# SY_HR08_MCU_SMT32_V1_1.net
KiCad netlist of a schematic drawn in Altium Designer
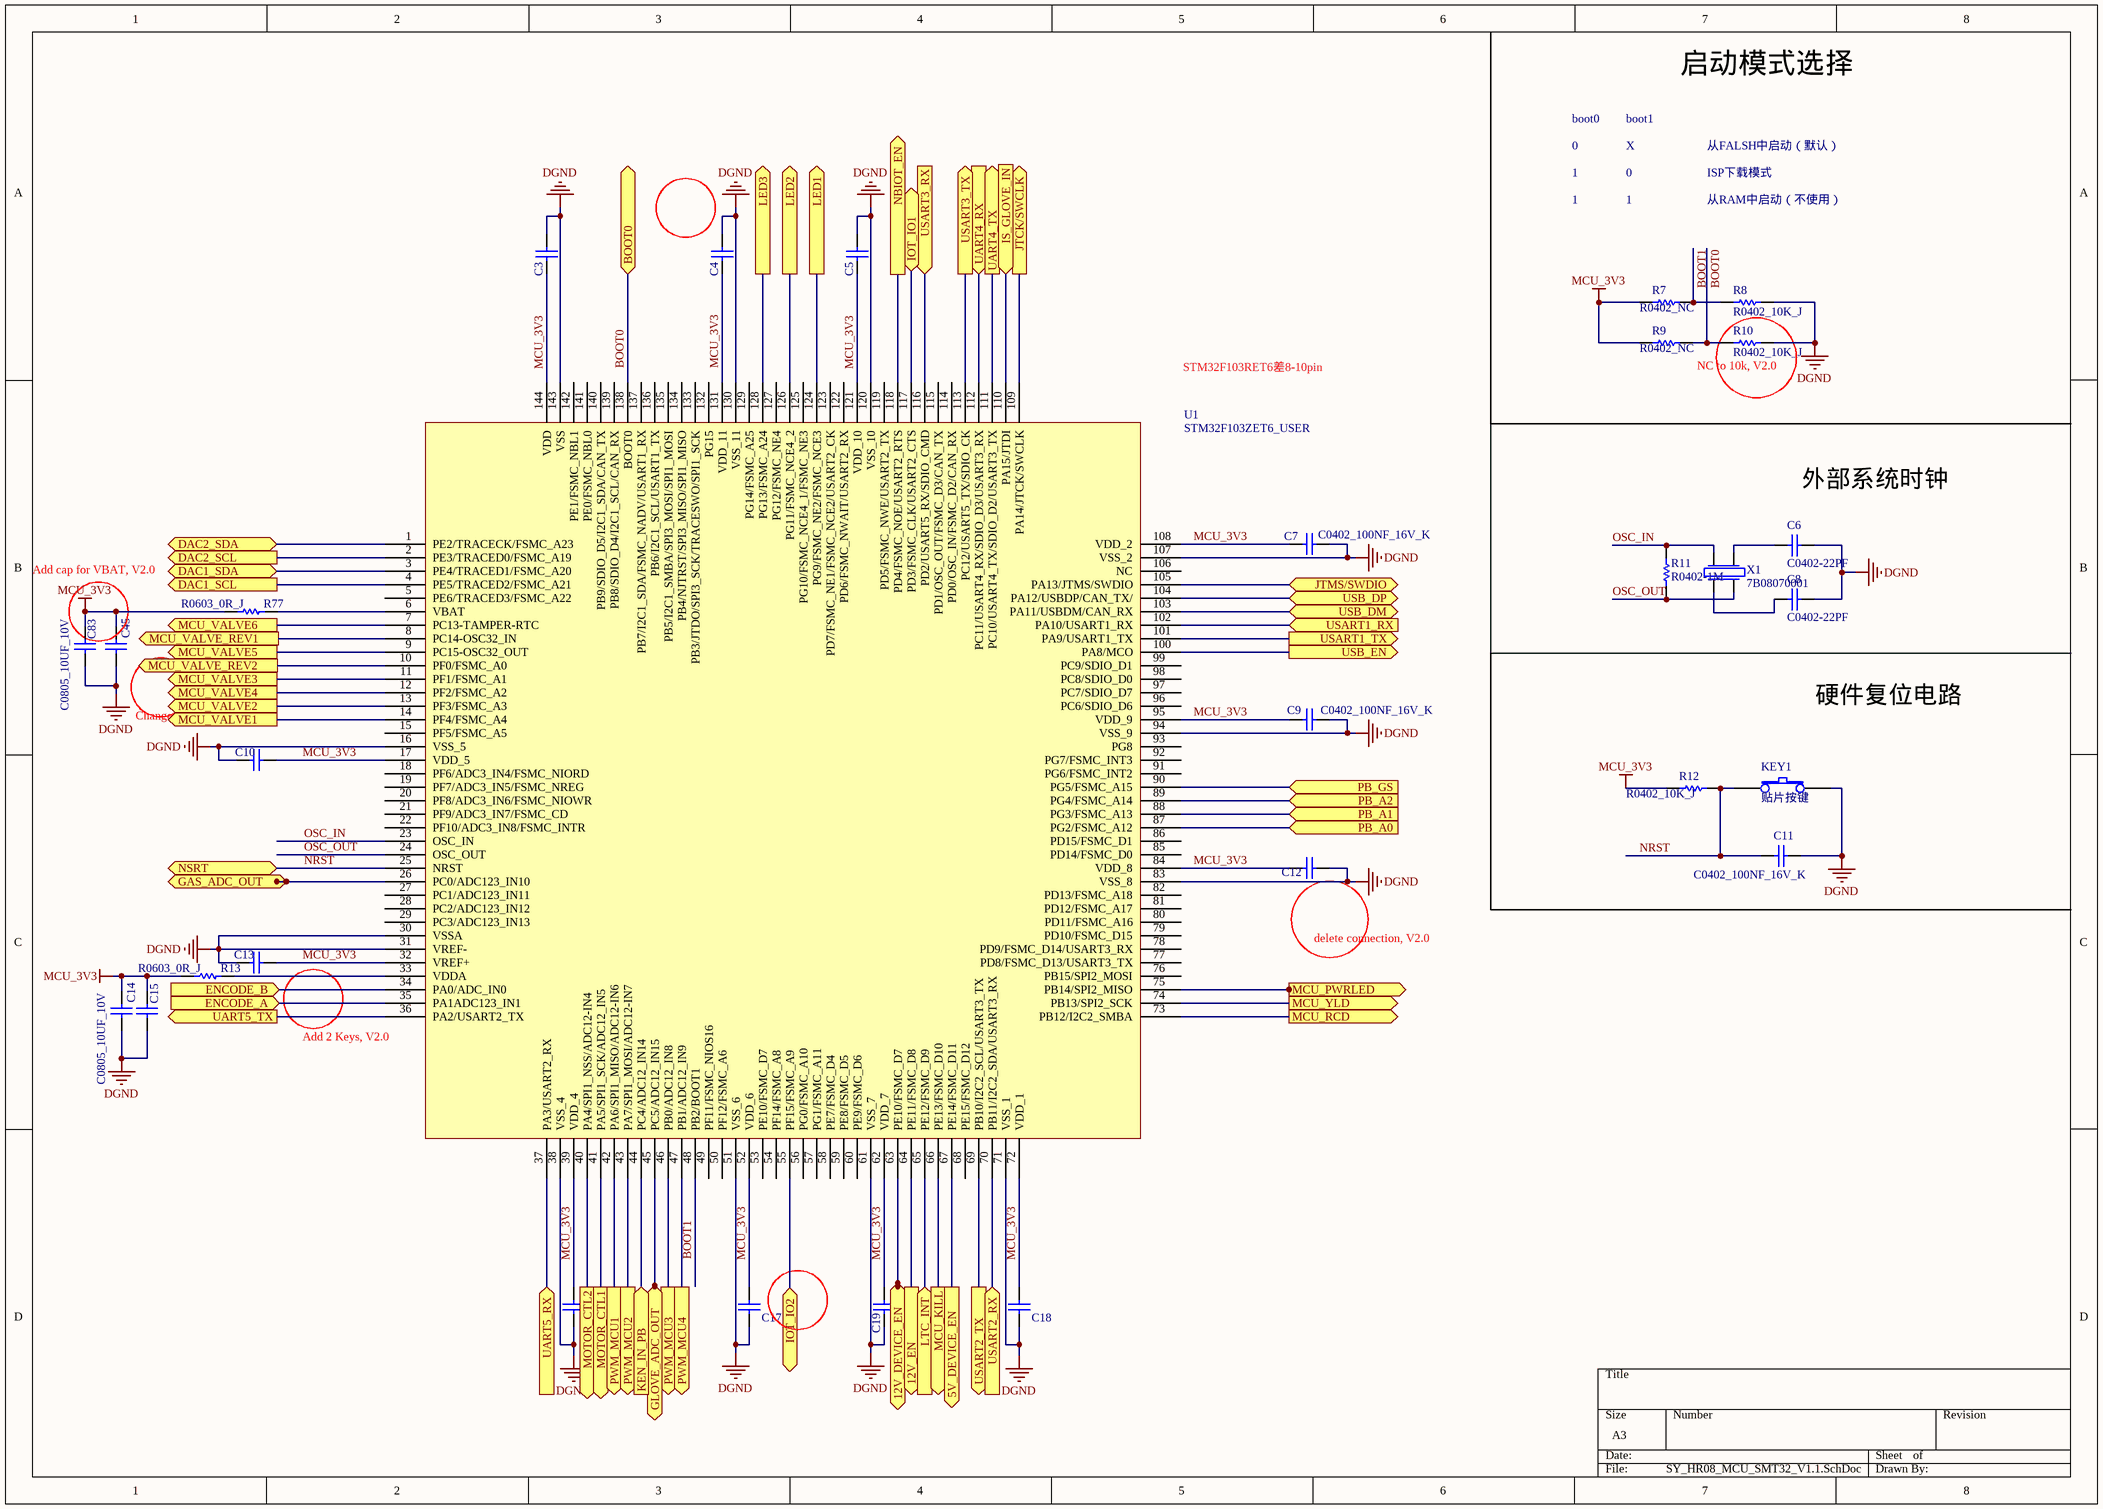
[diagram p0: SY_HR08_MCU_SMT32_V1.1.SchDoc]

(export (version "E")
  (design (tool "Eeschema 10.0.6"))
  (components
    (comp (ref "C3")
      (value "C0402_100NF_16V_K")
      (footprint "CAP0402_HQ")
      (description "电容_100nF_0402_X7R_16V_K")
      (libsource (lib "zhangky_sch") (part "C0402_100NF_16V_K"))
    )
    (comp (ref "C4")
      (value "C0402_100NF_16V_K")
      (footprint "CAP0402_HQ")
      (description "电容_100nF_0402_X7R_16V_K")
      (libsource (lib "zhangky_sch") (part "C0402_100NF_16V_K"))
    )
    (comp (ref "C5")
      (value "C0402_100NF_16V_K")
      (footprint "CAP0402_HQ")
      (description "电容_100nF_0402_X7R_16V_K")
      (libsource (lib "zhangky_sch") (part "C0402_100NF_16V_K"))
    )
    (comp (ref "C6")
      (value "C0402-22PF")
      (footprint "CAP0402_HQ")
      (description "电容_22pF_0402_C0G_50V_J")
      (libsource (lib "zhangky_sch") (part "C0402-22PF"))
    )
    (comp (ref "C7")
      (value "C0402_100NF_16V_K")
      (footprint "CAP0402_HQ")
      (description "电容_100nF_0402_X7R_16V_K")
      (libsource (lib "zhangky_sch") (part "C0402_100NF_16V_K"))
    )
    (comp (ref "C8")
      (value "C0402-22PF")
      (footprint "CAP0402_HQ")
      (description "电容_22pF_0402_C0G_50V_J")
      (libsource (lib "zhangky_sch") (part "C0402-22PF"))
    )
    (comp (ref "C9")
      (value "C0402_100NF_16V_K")
      (footprint "CAP0402_HQ")
      (description "电容_100nF_0402_X7R_16V_K")
      (libsource (lib "zhangky_sch") (part "C0402_100NF_16V_K"))
    )
    (comp (ref "C10")
      (value "C0402_100NF_16V_K")
      (footprint "CAP0402_HQ")
      (description "电容_100nF_0402_X7R_16V_K")
      (libsource (lib "zhangky_sch") (part "C0402_100NF_16V_K"))
    )
    (comp (ref "C11")
      (value "C0402_100NF_16V_K")
      (footprint "CAP0402_HQ")
      (description "电容_100nF_0402_X7R_16V_K")
      (libsource (lib "zhangky_sch") (part "C0402_100NF_16V_K"))
    )
    (comp (ref "C12")
      (value "C0402_100NF_16V_K")
      (footprint "CAP0402_HQ")
      (description "电容_100nF_0402_X7R_16V_K")
      (libsource (lib "zhangky_sch") (part "C0402_100NF_16V_K"))
    )
    (comp (ref "C13")
      (value "C0402_100NF_16V_K")
      (footprint "CAP0402_HQ")
      (description "电容_100nF_0402_X7R_16V_K")
      (libsource (lib "zhangky_sch") (part "C0402_100NF_16V_K"))
    )
    (comp (ref "C14")
      (value "C0805_10UF_10V")
      (footprint "CAP0805-B")
      (description "电容_10uF_0805_X5R_10V_K")
      (libsource (lib "zhangky_sch") (part "C0805_10UF_10V"))
    )
    (comp (ref "C15")
      (value "C0402_100NF_16V_K")
      (footprint "CAP0402_HQ")
      (description "电容_100nF_0402_X7R_16V_K")
      (libsource (lib "zhangky_sch") (part "C0402_100NF_16V_K"))
    )
    (comp (ref "C16")
      (value "C0402_100NF_16V_K")
      (footprint "CAP0402_HQ")
      (description "电容_100nF_0402_X7R_16V_K")
      (libsource (lib "zhangky_sch") (part "C0402_100NF_16V_K"))
    )
    (comp (ref "C17")
      (value "C0402_100NF_16V_K")
      (footprint "CAP0402_HQ")
      (description "电容_100nF_0402_X7R_16V_K")
      (libsource (lib "zhangky_sch") (part "C0402_100NF_16V_K"))
    )
    (comp (ref "C18")
      (value "C0402_100NF_16V_K")
      (footprint "CAP0402_HQ")
      (description "电容_100nF_0402_X7R_16V_K")
      (libsource (lib "zhangky_sch") (part "C0402_100NF_16V_K"))
    )
    (comp (ref "C19")
      (value "C0402_100NF_16V_K")
      (footprint "CAP0402_HQ")
      (description "电容_100nF_0402_X7R_16V_K")
      (libsource (lib "zhangky_sch") (part "C0402_100NF_16V_K"))
    )
    (comp (ref "C45")
      (value "C0805_10UF_10V")
      (footprint "CAP0805-B")
      (description "电容_10uF_0805_X5R_10V_K")
      (libsource (lib "zhangky_sch") (part "C0805_10UF_10V"))
    )
    (comp (ref "C83")
      (value "C0402_100NF_16V_K")
      (footprint "CAP0402_HQ")
      (description "电容_100nF_0402_X7R_16V_K")
      (libsource (lib "zhangky_sch") (part "C0402_100NF_16V_K"))
    )
    (comp (ref "KEY1")
      (value "贴片按键")
      (footprint "KEY_3x4x2")
      (description "KEY_3x4x2mm")
      (libsource (lib "zhangky_sch") (part "KEY_3x4x2"))
    )
    (comp (ref "R7")
      (value "R0402_NC")
      (footprint "RES0402_HQ_NC")
      (description "NC")
      (libsource (lib "zhangky_sch") (part "R0402_NC"))
    )
    (comp (ref "R8")
      (value "R0402_10K_J")
      (footprint "RES0402_HQ")
      (description "电阻10K(0402-0.0625W-J)")
      (libsource (lib "zhangky_sch") (part "R0402_10K_J"))
    )
    (comp (ref "R9")
      (value "R0402_NC")
      (footprint "RES0402_HQ_NC")
      (description "NC")
      (libsource (lib "zhangky_sch") (part "R0402_NC"))
    )
    (comp (ref "R10")
      (value "R0402_10K_J")
      (footprint "RES0402_HQ_NC")
      (description "NC")
      (libsource (lib "zhangky_sch") (part "R0402_NC"))
    )
    (comp (ref "R11")
      (value "R0402-1M")
      (footprint "RES0402_HQ")
      (description "电阻_1M(0402-0.0625W-J)")
      (libsource (lib "zhangky_sch") (part "R0402-1M"))
    )
    (comp (ref "R12")
      (value "R0402_10K_J")
      (footprint "RES0402_HQ")
      (description "电阻10K(0402-0.0625W-J)")
      (libsource (lib "zhangky_sch") (part "R0402_10K_J"))
    )
    (comp (ref "R13")
      (value "R0603_0R_J")
      (footprint "RES0603-A")
      (description "电阻0R(0603-0.1W-J)")
      (libsource (lib "zhangky_sch") (part "R0603_0R_J"))
    )
    (comp (ref "R77")
      (value "R0603_0R_J")
      (footprint "RES0603-A")
      (description "电阻0R(0603-0.1W-J)")
      (libsource (lib "zhangky_sch") (part "R0603_0R_J"))
    )
    (comp (ref "U1")
      (value "STM32F103ZET6_USER")
      (footprint "LQFP144_STM32F103")
      (libsource (lib "zhangky_sch") (part "STM32F103ZET6_USER"))
    )
    (comp (ref "X1")
      (value "7B08070001")
      (footprint "7B08070001")
      (description "TXC 5032 7B系列晶体")
      (fields (field (name "MANUFACTURER") "TXC"))
      (libsource (lib "zhangky_sch") (part "7B08070001"))
    )
  )
  (nets
    (net (code "1") (name "/5V_DEVICE_EN") (class "Default")
      (node (ref "U1") (pin "67") (pinfunction "PE14/FSMC_D11_67") (pintype "passive"))
    )
    (net (code "2") (name "/12V_DEVICE_EN") (class "Default")
      (node (ref "U1") (pin "63") (pinfunction "PE10/FSMC_D7_63") (pintype "passive"))
    )
    (net (code "3") (name "/12V_EN") (class "Default")
      (node (ref "U1") (pin "64") (pinfunction "PE11/FSMC_D8_64") (pintype "passive"))
    )
    (net (code "4") (name "/BOOT0") (class "Default")
      (node (ref "R10") (pin "1") (pinfunction "1_1") (pintype "passive"))
      (node (ref "R9") (pin "2") (pinfunction "2_2") (pintype "passive"))
      (node (ref "U1") (pin "138") (pinfunction "BOOT0_138") (pintype "passive"))
    )
    (net (code "5") (name "/BOOT1") (class "Default")
      (node (ref "R7") (pin "2") (pinfunction "2_2") (pintype "passive"))
      (node (ref "R8") (pin "1") (pinfunction "1_1") (pintype "passive"))
      (node (ref "U1") (pin "48") (pinfunction "PB2/BOOT1_48") (pintype "passive"))
    )
    (net (code "6") (name "/DAC1_SCL") (class "Default")
      (node (ref "U1") (pin "4") (pinfunction "PE5/TRACED2/FSMC_A21_4") (pintype "passive"))
    )
    (net (code "7") (name "/DAC1_SDA") (class "Default")
      (node (ref "U1") (pin "3") (pinfunction "PE4/TRACED1/FSMC_A20_3") (pintype "passive"))
    )
    (net (code "8") (name "/DAC2_SCL") (class "Default")
      (node (ref "U1") (pin "2") (pinfunction "PE3/TRACED0/FSMC_A19_2") (pintype "passive"))
    )
    (net (code "9") (name "/DAC2_SDA") (class "Default")
      (node (ref "U1") (pin "1") (pinfunction "PE2/TRACECK/FSMC_A23_1") (pintype "passive"))
    )
    (net (code "10") (name "/ENCODE_A") (class "Default")
      (node (ref "U1") (pin "35") (pinfunction "PA1ADC123_IN1_35") (pintype "passive"))
    )
    (net (code "11") (name "/ENCODE_B") (class "Default")
      (node (ref "U1") (pin "34") (pinfunction "PA0/ADC_IN0_34") (pintype "passive"))
    )
    (net (code "12") (name "/GAS_ADC_OUT") (class "Default")
      (node (ref "U1") (pin "26") (pinfunction "PC0/ADC123_IN10_26") (pintype "passive"))
    )
    (net (code "13") (name "/GLOVE_ADC_OUT") (class "Default")
      (node (ref "U1") (pin "45") (pinfunction "PC5/ADC12_IN15_45") (pintype "passive"))
    )
    (net (code "14") (name "/IOT_IO1") (class "Default")
      (node (ref "U1") (pin "117") (pinfunction "PD3/FSMC_CLK/USART2_CTS_117") (pintype "passive"))
    )
    (net (code "15") (name "/IOT_IO2") (class "Default")
      (node (ref "U1") (pin "55") (pinfunction "PF15/FSMC_A9_55") (pintype "passive"))
    )
    (net (code "16") (name "/IS_GLOVE_IN") (class "Default")
      (node (ref "U1") (pin "110") (pinfunction "PA15/JTDI_110") (pintype "passive"))
    )
    (net (code "17") (name "/JTCK{slash}SWCLK") (class "Default")
      (node (ref "U1") (pin "109") (pinfunction "PA14/JTCK/SWCLK_109") (pintype "passive"))
    )
    (net (code "18") (name "/JTMS{slash}SWDIO") (class "Default")
      (node (ref "U1") (pin "105") (pinfunction "PA13/JTMS/SWDIO_105") (pintype "passive"))
    )
    (net (code "19") (name "/KEN_IN_PB") (class "Default")
      (node (ref "U1") (pin "44") (pinfunction "PC4/ADC12_IN14_44") (pintype "passive"))
    )
    (net (code "20") (name "/LED1") (class "Default")
      (node (ref "U1") (pin "124") (pinfunction "PG9/FSMC_NE2/FSMC_NCE3_124") (pintype "passive"))
    )
    (net (code "21") (name "/LED2") (class "Default")
      (node (ref "U1") (pin "126") (pinfunction "PG11/FSMC_NCE4_2_126") (pintype "passive"))
    )
    (net (code "22") (name "/LED3") (class "Default")
      (node (ref "U1") (pin "128") (pinfunction "PG13/FSMC_A24_128") (pintype "passive"))
    )
    (net (code "23") (name "/LTC_INT") (class "Default")
      (node (ref "U1") (pin "65") (pinfunction "PE12/FSMC_D9_65") (pintype "passive"))
    )
    (net (code "24") (name "/MCU_KILL") (class "Default")
      (node (ref "U1") (pin "66") (pinfunction "PE13/FSMC_D10_66") (pintype "passive"))
    )
    (net (code "25") (name "/MCU_PWRLED") (class "Default")
      (node (ref "U1") (pin "75") (pinfunction "PB14/SPI2_MISO_75") (pintype "passive"))
    )
    (net (code "26") (name "/MCU_RCD") (class "Default")
      (node (ref "U1") (pin "73") (pinfunction "PB12/I2C2_SMBA_73") (pintype "passive"))
    )
    (net (code "27") (name "/MCU_VALVE1") (class "Default")
      (node (ref "U1") (pin "14") (pinfunction "PF4/FSMC_A4_14") (pintype "passive"))
    )
    (net (code "28") (name "/MCU_VALVE2") (class "Default")
      (node (ref "U1") (pin "13") (pinfunction "PF3/FSMC_A3_13") (pintype "passive"))
    )
    (net (code "29") (name "/MCU_VALVE3") (class "Default")
      (node (ref "U1") (pin "11") (pinfunction "PF1/FSMC_A1_11") (pintype "passive"))
    )
    (net (code "30") (name "/MCU_VALVE4") (class "Default")
      (node (ref "U1") (pin "12") (pinfunction "PF2/FSMC_A2_12") (pintype "passive"))
    )
    (net (code "31") (name "/MCU_VALVE5") (class "Default")
      (node (ref "U1") (pin "9") (pinfunction "PC15-OSC32_OUT_9") (pintype "passive"))
    )
    (net (code "32") (name "/MCU_VALVE6") (class "Default")
      (node (ref "U1") (pin "7") (pinfunction "PC13-TAMPER-RTC_7") (pintype "passive"))
    )
    (net (code "33") (name "/MCU_VALVE_REV1") (class "Default")
      (node (ref "U1") (pin "8") (pinfunction "PC14-OSC32_IN_8") (pintype "passive"))
    )
    (net (code "34") (name "/MCU_VALVE_REV2") (class "Default")
      (node (ref "U1") (pin "10") (pinfunction "PF0/FSMC_A0_10") (pintype "passive"))
    )
    (net (code "35") (name "/MCU_YLD") (class "Default")
      (node (ref "U1") (pin "74") (pinfunction "PB13/SPI2_SCK_74") (pintype "passive"))
    )
    (net (code "36") (name "/MOTOR_CTL1") (class "Default")
      (node (ref "U1") (pin "41") (pinfunction "PA5/SPI1_SCK/ADC12_IN5_41") (pintype "passive"))
    )
    (net (code "37") (name "/MOTOR_CTL2") (class "Default")
      (node (ref "U1") (pin "40") (pinfunction "PA4/SPI1_NSS/ADC12-IN4_40") (pintype "passive"))
    )
    (net (code "38") (name "/NBIOT_EN") (class "Default")
      (node (ref "U1") (pin "118") (pinfunction "PD4/FSMC_NOE/USART2_RTS_118") (pintype "passive"))
    )
    (net (code "39") (name "/NRST") (class "Default")
      (node (ref "C11") (pin "1") (pinfunction "1_1") (pintype "passive"))
      (node (ref "KEY1") (pin "1") (pinfunction "1_1") (pintype "passive"))
      (node (ref "R12") (pin "2") (pinfunction "2_2") (pintype "passive"))
      (node (ref "U1") (pin "25") (pinfunction "NRST_25") (pintype "passive"))
    )
    (net (code "40") (name "/OSC_IN") (class "Default")
      (node (ref "R11") (pin "2") (pinfunction "2_2") (pintype "passive"))
      (node (ref "U1") (pin "23") (pinfunction "OSC_IN_23") (pintype "passive"))
      (node (ref "X1") (pin "3") (pinfunction "3_3") (pintype "passive"))
    )
    (net (code "41") (name "/OSC_OUT") (class "Default")
      (node (ref "R11") (pin "1") (pinfunction "1_1") (pintype "passive"))
      (node (ref "U1") (pin "24") (pinfunction "OSC_OUT_24") (pintype "passive"))
      (node (ref "X1") (pin "1") (pinfunction "1_1") (pintype "passive"))
    )
    (net (code "42") (name "/PB_A0") (class "Default")
      (node (ref "U1") (pin "87") (pinfunction "PG2/FSMC_A12_87") (pintype "passive"))
    )
    (net (code "43") (name "/PB_A1") (class "Default")
      (node (ref "U1") (pin "88") (pinfunction "PG3/FSMC_A13_88") (pintype "passive"))
    )
    (net (code "44") (name "/PB_A2") (class "Default")
      (node (ref "U1") (pin "89") (pinfunction "PG4/FSMC_A14_89") (pintype "passive"))
    )
    (net (code "45") (name "/PB_GS") (class "Default")
      (node (ref "U1") (pin "90") (pinfunction "PG5/FSMC_A15_90") (pintype "passive"))
    )
    (net (code "46") (name "/PWM_MCU1") (class "Default")
      (node (ref "U1") (pin "42") (pinfunction "PA6/SPI1_MISO/ADC12-IN6_42") (pintype "passive"))
    )
    (net (code "47") (name "/PWM_MCU2") (class "Default")
      (node (ref "U1") (pin "43") (pinfunction "PA7/SPI1_MOSI/ADC12-IN7_43") (pintype "passive"))
    )
    (net (code "48") (name "/PWM_MCU3") (class "Default")
      (node (ref "U1") (pin "46") (pinfunction "PB0/ADC12_IN8_46") (pintype "passive"))
    )
    (net (code "49") (name "/PWM_MCU4") (class "Default")
      (node (ref "U1") (pin "47") (pinfunction "PB1/ADC12_IN9_47") (pintype "passive"))
    )
    (net (code "50") (name "/UART4_RX") (class "Default")
      (node (ref "U1") (pin "112") (pinfunction "PC11/USART4_RX/SDIO_D3/USART3_RX_112") (pintype "passive"))
    )
    (net (code "51") (name "/UART4_TX") (class "Default")
      (node (ref "U1") (pin "111") (pinfunction "PC10/USART4_TX/SDIO_D2/USART3_TX_111") (pintype "passive"))
    )
    (net (code "52") (name "/UART5_RX") (class "Default")
      (node (ref "U1") (pin "37") (pinfunction "PA3/USART2_RX_37") (pintype "passive"))
    )
    (net (code "53") (name "/UART5_TX") (class "Default")
      (node (ref "U1") (pin "36") (pinfunction "PA2/USART2_TX_36") (pintype "passive"))
    )
    (net (code "54") (name "/USART1_RX") (class "Default")
      (node (ref "U1") (pin "102") (pinfunction "PA10/USART1_RX_102") (pintype "passive"))
    )
    (net (code "55") (name "/USART1_TX") (class "Default")
      (node (ref "U1") (pin "101") (pinfunction "PA9/USART1_TX_101") (pintype "passive"))
    )
    (net (code "56") (name "/USART2_RX") (class "Default")
      (node (ref "U1") (pin "70") (pinfunction "PB11/I2C2_SDA/USART3_RX_70") (pintype "passive"))
    )
    (net (code "57") (name "/USART2_TX") (class "Default")
      (node (ref "U1") (pin "69") (pinfunction "PB10/I2C2_SCL/USART3_TX_69") (pintype "passive"))
    )
    (net (code "58") (name "/USART3_RX") (class "Default")
      (node (ref "U1") (pin "116") (pinfunction "PD2/USART5_RX/SDIO_CMD_116") (pintype "passive"))
    )
    (net (code "59") (name "/USART3_TX") (class "Default")
      (node (ref "U1") (pin "113") (pinfunction "PC12/USART5_TX/SDIO_CK_113") (pintype "passive"))
    )
    (net (code "60") (name "/USB_DM") (class "Default")
      (node (ref "U1") (pin "103") (pinfunction "PA11/USBDM/CAN_RX_103") (pintype "passive"))
    )
    (net (code "61") (name "/USB_DP") (class "Default")
      (node (ref "U1") (pin "104") (pinfunction "PA12/USBDP/CAN_TX/_104") (pintype "passive"))
    )
    (net (code "62") (name "/USB_EN") (class "Default")
      (node (ref "U1") (pin "100") (pinfunction "PA8/MCO_100") (pintype "passive"))
    )
    (net (code "63") (name "DGND") (class "Default")
      (node (ref "C10") (pin "2") (pinfunction "2_2") (pintype "passive"))
      (node (ref "C11") (pin "2") (pinfunction "2_2") (pintype "passive"))
      (node (ref "C12") (pin "2") (pinfunction "2_2") (pintype "passive"))
      (node (ref "C13") (pin "2") (pinfunction "2_2") (pintype "passive"))
      (node (ref "C14") (pin "1") (pinfunction "1_1") (pintype "passive"))
      (node (ref "C15") (pin "2") (pinfunction "2_2") (pintype "passive"))
      (node (ref "C16") (pin "2") (pinfunction "2_2") (pintype "passive"))
      (node (ref "C17") (pin "2") (pinfunction "2_2") (pintype "passive"))
      (node (ref "C18") (pin "2") (pinfunction "2_2") (pintype "passive"))
      (node (ref "C19") (pin "2") (pinfunction "2_2") (pintype "passive"))
      (node (ref "C3") (pin "2") (pinfunction "2_2") (pintype "passive"))
      (node (ref "C4") (pin "2") (pinfunction "2_2") (pintype "passive"))
      (node (ref "C45") (pin "1") (pinfunction "1_1") (pintype "passive"))
      (node (ref "C5") (pin "2") (pinfunction "2_2") (pintype "passive"))
      (node (ref "C6") (pin "2") (pinfunction "2_2") (pintype "passive"))
      (node (ref "C7") (pin "2") (pinfunction "2_2") (pintype "passive"))
      (node (ref "C8") (pin "2") (pinfunction "2_2") (pintype "passive"))
      (node (ref "C83") (pin "2") (pinfunction "2_2") (pintype "passive"))
      (node (ref "C9") (pin "2") (pinfunction "2_2") (pintype "passive"))
      (node (ref "KEY1") (pin "2") (pinfunction "2_2") (pintype "passive"))
      (node (ref "R10") (pin "2") (pinfunction "2_2") (pintype "passive"))
      (node (ref "R8") (pin "2") (pinfunction "2_2") (pintype "passive"))
      (node (ref "U1") (pin "107") (pinfunction "VSS_2_107") (pintype "passive"))
      (node (ref "U1") (pin "120") (pinfunction "VSS_10_120") (pintype "passive"))
      (node (ref "U1") (pin "130") (pinfunction "VSS_11_130") (pintype "passive"))
      (node (ref "U1") (pin "143") (pinfunction "VSS_143") (pintype "passive"))
      (node (ref "U1") (pin "16") (pinfunction "VSS_5_16") (pintype "passive"))
      (node (ref "U1") (pin "30") (pinfunction "VSSA_30") (pintype "passive"))
      (node (ref "U1") (pin "31") (pinfunction "VREF-_31") (pintype "passive"))
      (node (ref "U1") (pin "38") (pinfunction "VSS_4_38") (pintype "passive"))
      (node (ref "U1") (pin "51") (pinfunction "VSS_6_51") (pintype "passive"))
      (node (ref "U1") (pin "61") (pinfunction "VSS_7_61") (pintype "passive"))
      (node (ref "U1") (pin "71") (pinfunction "VSS_1_71") (pintype "passive"))
      (node (ref "U1") (pin "83") (pinfunction "VSS_8_83") (pintype "passive"))
      (node (ref "U1") (pin "94") (pinfunction "VSS_9_94") (pintype "passive"))
    )
    (net (code "64") (name "MCU_3V3") (class "Default")
      (node (ref "C10") (pin "1") (pinfunction "1_1") (pintype "passive"))
      (node (ref "C12") (pin "1") (pinfunction "1_1") (pintype "passive"))
      (node (ref "C13") (pin "1") (pinfunction "1_1") (pintype "passive"))
      (node (ref "C14") (pin "2") (pinfunction "2_2") (pintype "passive"))
      (node (ref "C15") (pin "1") (pinfunction "1_1") (pintype "passive"))
      (node (ref "C16") (pin "1") (pinfunction "1_1") (pintype "passive"))
      (node (ref "C17") (pin "1") (pinfunction "1_1") (pintype "passive"))
      (node (ref "C18") (pin "1") (pinfunction "1_1") (pintype "passive"))
      (node (ref "C19") (pin "1") (pinfunction "1_1") (pintype "passive"))
      (node (ref "C3") (pin "1") (pinfunction "1_1") (pintype "passive"))
      (node (ref "C4") (pin "1") (pinfunction "1_1") (pintype "passive"))
      (node (ref "C45") (pin "2") (pinfunction "2_2") (pintype "passive"))
      (node (ref "C5") (pin "1") (pinfunction "1_1") (pintype "passive"))
      (node (ref "C7") (pin "1") (pinfunction "1_1") (pintype "passive"))
      (node (ref "C83") (pin "1") (pinfunction "1_1") (pintype "passive"))
      (node (ref "C9") (pin "1") (pinfunction "1_1") (pintype "passive"))
      (node (ref "R12") (pin "1") (pinfunction "1_1") (pintype "passive"))
      (node (ref "R13") (pin "1") (pinfunction "1_1") (pintype "passive"))
      (node (ref "R7") (pin "1") (pinfunction "1_1") (pintype "passive"))
      (node (ref "R77") (pin "1") (pinfunction "1_1") (pintype "passive"))
      (node (ref "R9") (pin "1") (pinfunction "1_1") (pintype "passive"))
      (node (ref "U1") (pin "108") (pinfunction "VDD_2_108") (pintype "passive"))
      (node (ref "U1") (pin "121") (pinfunction "VDD_10_121") (pintype "passive"))
      (node (ref "U1") (pin "131") (pinfunction "VDD_11_131") (pintype "passive"))
      (node (ref "U1") (pin "144") (pinfunction "VDD_144") (pintype "passive"))
      (node (ref "U1") (pin "17") (pinfunction "VDD_5_17") (pintype "passive"))
      (node (ref "U1") (pin "32") (pinfunction "VREF+_32") (pintype "passive"))
      (node (ref "U1") (pin "39") (pinfunction "VDD_4_39") (pintype "passive"))
      (node (ref "U1") (pin "52") (pinfunction "VDD_6_52") (pintype "passive"))
      (node (ref "U1") (pin "62") (pinfunction "VDD_7_62") (pintype "passive"))
      (node (ref "U1") (pin "72") (pinfunction "VDD_1_72") (pintype "passive"))
      (node (ref "U1") (pin "84") (pinfunction "VDD_8_84") (pintype "passive"))
      (node (ref "U1") (pin "95") (pinfunction "VDD_9_95") (pintype "passive"))
    )
    (net (code "65") (name "Net-(C6-Pad1)") (class "Default")
      (node (ref "C6") (pin "1") (pinfunction "1_1") (pintype "passive"))
      (node (ref "X1") (pin "2") (pinfunction "2_2") (pintype "passive"))
    )
    (net (code "66") (name "Net-(C8-Pad1)") (class "Default")
      (node (ref "C8") (pin "1") (pinfunction "1_1") (pintype "passive"))
      (node (ref "X1") (pin "4") (pinfunction "4_4") (pintype "passive"))
    )
    (net (code "67") (name "Net-(U1-VBAT)") (class "Default")
      (node (ref "R77") (pin "2") (pinfunction "2_2") (pintype "passive"))
      (node (ref "U1") (pin "6") (pinfunction "VBAT_6") (pintype "passive"))
    )
    (net (code "68") (name "Net-(U1-VDDA)") (class "Default")
      (node (ref "R13") (pin "2") (pinfunction "2_2") (pintype "passive"))
      (node (ref "U1") (pin "33") (pinfunction "VDDA_33") (pintype "passive"))
    )
    (net (code "69") (name "unconnected-(U1-NC-Pad106)") (class "Default")
      (node (ref "U1") (pin "106") (pinfunction "NC_106") (pintype "passive"))
    )
    (net (code "70") (name "unconnected-(U1-PB3{slash}JTDO{slash}SPI3_SCK{slash}TRACESWO{slash}SPI1_SCK-Pad133)") (class "Default")
      (node (ref "U1") (pin "133") (pinfunction "PB3/JTDO/SPI3_SCK/TRACESWO/SPI1_SCK_133") (pintype "passive"))
    )
    (net (code "71") (name "unconnected-(U1-PB4{slash}NJTRST{slash}SPI3_MISO{slash}SPI1_MISO-Pad134)") (class "Default")
      (node (ref "U1") (pin "134") (pinfunction "PB4/NJTRST/SPI3_MISO/SPI1_MISO_134") (pintype "passive"))
    )
    (net (code "72") (name "unconnected-(U1-PB5{slash}I2C1_SMBA{slash}SPI3_MOSI{slash}SPI1_MOSI-Pad135)") (class "Default")
      (node (ref "U1") (pin "135") (pinfunction "PB5/I2C1_SMBA/SPI3_MOSI/SPI1_MOSI_135") (pintype "passive"))
    )
    (net (code "73") (name "unconnected-(U1-PB6{slash}I2C1_SCL{slash}USART1_TX-Pad136)") (class "Default")
      (node (ref "U1") (pin "136") (pinfunction "PB6/I2C1_SCL/USART1_TX_136") (pintype "passive"))
    )
    (net (code "74") (name "unconnected-(U1-PB7{slash}I2C1_SDA{slash}FSMC_NADV{slash}USART1_RX-Pad137)") (class "Default")
      (node (ref "U1") (pin "137") (pinfunction "PB7/I2C1_SDA/FSMC_NADV/USART1_RX_137") (pintype "passive"))
    )
    (net (code "75") (name "unconnected-(U1-PB8{slash}SDIO_D4{slash}I2C1_SCL{slash}CAN_RX-Pad139)") (class "Default")
      (node (ref "U1") (pin "139") (pinfunction "PB8/SDIO_D4/I2C1_SCL/CAN_RX_139") (pintype "passive"))
    )
    (net (code "76") (name "unconnected-(U1-PB9{slash}SDIO_D5{slash}I2C1_SDA{slash}CAN_TX-Pad140)") (class "Default")
      (node (ref "U1") (pin "140") (pinfunction "PB9/SDIO_D5/I2C1_SDA/CAN_TX_140") (pintype "passive"))
    )
    (net (code "77") (name "unconnected-(U1-PB15{slash}SPI2_MOSI-Pad76)") (class "Default")
      (node (ref "U1") (pin "76") (pinfunction "PB15/SPI2_MOSI_76") (pintype "passive"))
    )
    (net (code "78") (name "unconnected-(U1-PC1{slash}ADC123_IN11-Pad27)") (class "Default")
      (node (ref "U1") (pin "27") (pinfunction "PC1/ADC123_IN11_27") (pintype "passive"))
    )
    (net (code "79") (name "unconnected-(U1-PC2{slash}ADC123_IN12-Pad28)") (class "Default")
      (node (ref "U1") (pin "28") (pinfunction "PC2/ADC123_IN12_28") (pintype "passive"))
    )
    (net (code "80") (name "unconnected-(U1-PC3{slash}ADC123_IN13-Pad29)") (class "Default")
      (node (ref "U1") (pin "29") (pinfunction "PC3/ADC123_IN13_29") (pintype "passive"))
    )
    (net (code "81") (name "unconnected-(U1-PC6{slash}SDIO_D6-Pad96)") (class "Default")
      (node (ref "U1") (pin "96") (pinfunction "PC6/SDIO_D6_96") (pintype "passive"))
    )
    (net (code "82") (name "unconnected-(U1-PC7{slash}SDIO_D7-Pad97)") (class "Default")
      (node (ref "U1") (pin "97") (pinfunction "PC7/SDIO_D7_97") (pintype "passive"))
    )
    (net (code "83") (name "unconnected-(U1-PC8{slash}SDIO_D0-Pad98)") (class "Default")
      (node (ref "U1") (pin "98") (pinfunction "PC8/SDIO_D0_98") (pintype "passive"))
    )
    (net (code "84") (name "unconnected-(U1-PC9{slash}SDIO_D1-Pad99)") (class "Default")
      (node (ref "U1") (pin "99") (pinfunction "PC9/SDIO_D1_99") (pintype "passive"))
    )
    (net (code "85") (name "unconnected-(U1-PD0{slash}OSC_IN{slash}FSMC_D2{slash}CAN_RX-Pad114)") (class "Default")
      (node (ref "U1") (pin "114") (pinfunction "PD0/OSC_IN/FSMC_D2/CAN_RX_114") (pintype "passive"))
    )
    (net (code "86") (name "unconnected-(U1-PD1{slash}OSC_OUT{slash}FSMC_D3{slash}CAN_TX-Pad115)") (class "Default")
      (node (ref "U1") (pin "115") (pinfunction "PD1/OSC_OUT/FSMC_D3/CAN_TX_115") (pintype "passive"))
    )
    (net (code "87") (name "unconnected-(U1-PD5{slash}FSMC_NWE{slash}USART2_TX-Pad119)") (class "Default")
      (node (ref "U1") (pin "119") (pinfunction "PD5/FSMC_NWE/USART2_TX_119") (pintype "passive"))
    )
    (net (code "88") (name "unconnected-(U1-PD6{slash}FSMC_NWAIT{slash}USART2_RX-Pad122)") (class "Default")
      (node (ref "U1") (pin "122") (pinfunction "PD6/FSMC_NWAIT/USART2_RX_122") (pintype "passive"))
    )
    (net (code "89") (name "unconnected-(U1-PD7{slash}FSMC_NE1{slash}FSMC_NCE2{slash}USART2_CK-Pad123)") (class "Default")
      (node (ref "U1") (pin "123") (pinfunction "PD7/FSMC_NE1/FSMC_NCE2/USART2_CK_123") (pintype "passive"))
    )
    (net (code "90") (name "unconnected-(U1-PD8{slash}FSMC_D13{slash}USART3_TX-Pad77)") (class "Default")
      (node (ref "U1") (pin "77") (pinfunction "PD8/FSMC_D13/USART3_TX_77") (pintype "passive"))
    )
    (net (code "91") (name "unconnected-(U1-PD9{slash}FSMC_D14{slash}USART3_RX-Pad78)") (class "Default")
      (node (ref "U1") (pin "78") (pinfunction "PD9/FSMC_D14/USART3_RX_78") (pintype "passive"))
    )
    (net (code "92") (name "unconnected-(U1-PD10{slash}FSMC_D15-Pad79)") (class "Default")
      (node (ref "U1") (pin "79") (pinfunction "PD10/FSMC_D15_79") (pintype "passive"))
    )
    (net (code "93") (name "unconnected-(U1-PD11{slash}FSMC_A16-Pad80)") (class "Default")
      (node (ref "U1") (pin "80") (pinfunction "PD11/FSMC_A16_80") (pintype "passive"))
    )
    (net (code "94") (name "unconnected-(U1-PD12{slash}FSMC_A17-Pad81)") (class "Default")
      (node (ref "U1") (pin "81") (pinfunction "PD12/FSMC_A17_81") (pintype "passive"))
    )
    (net (code "95") (name "unconnected-(U1-PD13{slash}FSMC_A18-Pad82)") (class "Default")
      (node (ref "U1") (pin "82") (pinfunction "PD13/FSMC_A18_82") (pintype "passive"))
    )
    (net (code "96") (name "unconnected-(U1-PD14{slash}FSMC_D0-Pad85)") (class "Default")
      (node (ref "U1") (pin "85") (pinfunction "PD14/FSMC_D0_85") (pintype "passive"))
    )
    (net (code "97") (name "unconnected-(U1-PD15{slash}FSMC_D1-Pad86)") (class "Default")
      (node (ref "U1") (pin "86") (pinfunction "PD15/FSMC_D1_86") (pintype "passive"))
    )
    (net (code "98") (name "unconnected-(U1-PE0{slash}FSMC_NBL0-Pad141)") (class "Default")
      (node (ref "U1") (pin "141") (pinfunction "PE0/FSMC_NBL0_141") (pintype "passive"))
    )
    (net (code "99") (name "unconnected-(U1-PE1{slash}FSMC_NBL1-Pad142)") (class "Default")
      (node (ref "U1") (pin "142") (pinfunction "PE1/FSMC_NBL1_142") (pintype "passive"))
    )
    (net (code "100") (name "unconnected-(U1-PE6{slash}TRACED3{slash}FSMC_A22-Pad5)") (class "Default")
      (node (ref "U1") (pin "5") (pinfunction "PE6/TRACED3/FSMC_A22_5") (pintype "passive"))
    )
    (net (code "101") (name "unconnected-(U1-PE7{slash}FSMC_D4-Pad58)") (class "Default")
      (node (ref "U1") (pin "58") (pinfunction "PE7/FSMC_D4_58") (pintype "passive"))
    )
    (net (code "102") (name "unconnected-(U1-PE8{slash}FSMC_D5-Pad59)") (class "Default")
      (node (ref "U1") (pin "59") (pinfunction "PE8/FSMC_D5_59") (pintype "passive"))
    )
    (net (code "103") (name "unconnected-(U1-PE9{slash}FSMC_D6-Pad60)") (class "Default")
      (node (ref "U1") (pin "60") (pinfunction "PE9/FSMC_D6_60") (pintype "passive"))
    )
    (net (code "104") (name "unconnected-(U1-PE10{slash}FSMC_D7-Pad53)") (class "Default")
      (node (ref "U1") (pin "53") (pinfunction "PE10/FSMC_D7_53") (pintype "passive"))
    )
    (net (code "105") (name "unconnected-(U1-PE15{slash}FSMC_D12-Pad68)") (class "Default")
      (node (ref "U1") (pin "68") (pinfunction "PE15/FSMC_D12_68") (pintype "passive"))
    )
    (net (code "106") (name "unconnected-(U1-PF5{slash}FSMC_A5-Pad15)") (class "Default")
      (node (ref "U1") (pin "15") (pinfunction "PF5/FSMC_A5_15") (pintype "passive"))
    )
    (net (code "107") (name "unconnected-(U1-PF6{slash}ADC3_IN4{slash}FSMC_NIORD-Pad18)") (class "Default")
      (node (ref "U1") (pin "18") (pinfunction "PF6/ADC3_IN4/FSMC_NIORD_18") (pintype "passive"))
    )
    (net (code "108") (name "unconnected-(U1-PF7{slash}ADC3_IN5{slash}FSMC_NREG-Pad19)") (class "Default")
      (node (ref "U1") (pin "19") (pinfunction "PF7/ADC3_IN5/FSMC_NREG_19") (pintype "passive"))
    )
    (net (code "109") (name "unconnected-(U1-PF8{slash}ADC3_IN6{slash}FSMC_NIOWR-Pad20)") (class "Default")
      (node (ref "U1") (pin "20") (pinfunction "PF8/ADC3_IN6/FSMC_NIOWR_20") (pintype "passive"))
    )
    (net (code "110") (name "unconnected-(U1-PF9{slash}ADC3_IN7{slash}FSMC_CD-Pad21)") (class "Default")
      (node (ref "U1") (pin "21") (pinfunction "PF9/ADC3_IN7/FSMC_CD_21") (pintype "passive"))
    )
    (net (code "111") (name "unconnected-(U1-PF10{slash}ADC3_IN8{slash}FSMC_INTR-Pad22)") (class "Default")
      (node (ref "U1") (pin "22") (pinfunction "PF10/ADC3_IN8/FSMC_INTR_22") (pintype "passive"))
    )
    (net (code "112") (name "unconnected-(U1-PF11{slash}FSMC_NIOS16-Pad49)") (class "Default")
      (node (ref "U1") (pin "49") (pinfunction "PF11/FSMC_NIOS16_49") (pintype "passive"))
    )
    (net (code "113") (name "unconnected-(U1-PF12{slash}FSMC_A6-Pad50)") (class "Default")
      (node (ref "U1") (pin "50") (pinfunction "PF12/FSMC_A6_50") (pintype "passive"))
    )
    (net (code "114") (name "unconnected-(U1-PF14{slash}FSMC_A8-Pad54)") (class "Default")
      (node (ref "U1") (pin "54") (pinfunction "PF14/FSMC_A8_54") (pintype "passive"))
    )
    (net (code "115") (name "unconnected-(U1-PG0{slash}FSMC_A10-Pad56)") (class "Default")
      (node (ref "U1") (pin "56") (pinfunction "PG0/FSMC_A10_56") (pintype "passive"))
    )
    (net (code "116") (name "unconnected-(U1-PG1{slash}FSMC_A11-Pad57)") (class "Default")
      (node (ref "U1") (pin "57") (pinfunction "PG1/FSMC_A11_57") (pintype "passive"))
    )
    (net (code "117") (name "unconnected-(U1-PG6{slash}FSMC_INT2-Pad91)") (class "Default")
      (node (ref "U1") (pin "91") (pinfunction "PG6/FSMC_INT2_91") (pintype "passive"))
    )
    (net (code "118") (name "unconnected-(U1-PG7{slash}FSMC_INT3-Pad92)") (class "Default")
      (node (ref "U1") (pin "92") (pinfunction "PG7/FSMC_INT3_92") (pintype "passive"))
    )
    (net (code "119") (name "unconnected-(U1-PG8-Pad93)") (class "Default")
      (node (ref "U1") (pin "93") (pinfunction "PG8_93") (pintype "passive"))
    )
    (net (code "120") (name "unconnected-(U1-PG10{slash}FSMC_NCE4_1{slash}FSMC_NE3-Pad125)") (class "Default")
      (node (ref "U1") (pin "125") (pinfunction "PG10/FSMC_NCE4_1/FSMC_NE3_125") (pintype "passive"))
    )
    (net (code "121") (name "unconnected-(U1-PG12{slash}FSMC_NE4-Pad127)") (class "Default")
      (node (ref "U1") (pin "127") (pinfunction "PG12/FSMC_NE4_127") (pintype "passive"))
    )
    (net (code "122") (name "unconnected-(U1-PG14{slash}FSMC_A25-Pad129)") (class "Default")
      (node (ref "U1") (pin "129") (pinfunction "PG14/FSMC_A25_129") (pintype "passive"))
    )
    (net (code "123") (name "unconnected-(U1-PG15-Pad132)") (class "Default")
      (node (ref "U1") (pin "132") (pinfunction "PG15_132") (pintype "passive"))
    )
  )
)
